# Sheet4.net
KiCad netlist of a schematic drawn in Altium Designer
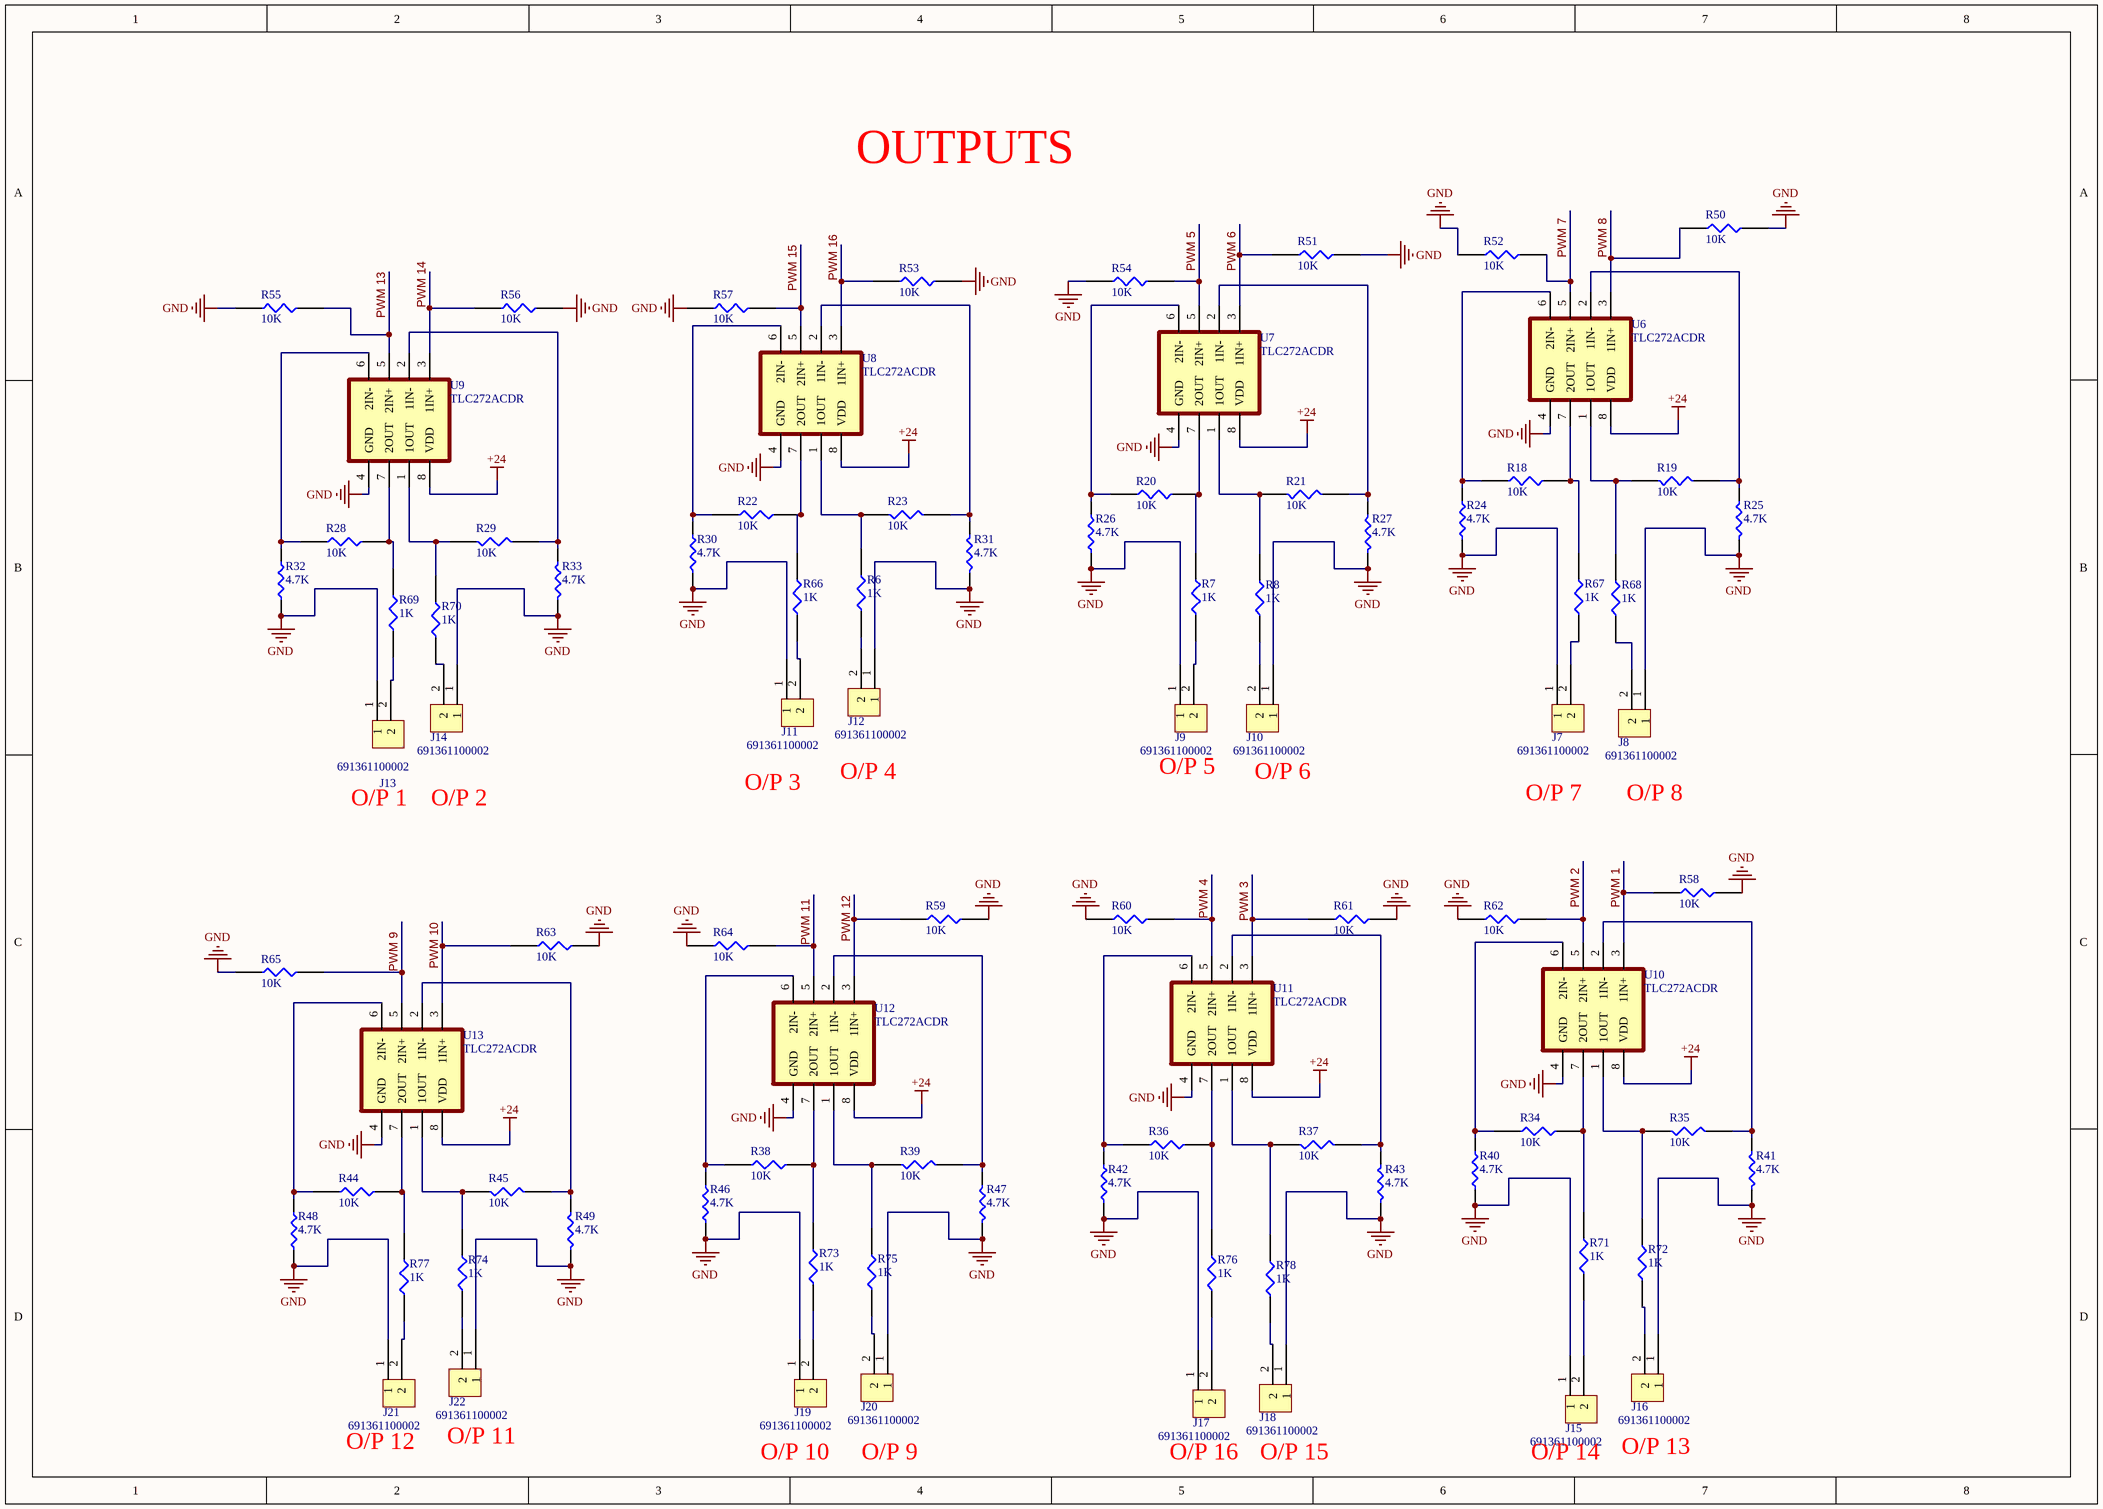
[diagram p0: Sheet4.SchDoc]

(export (version "E")
  (design (tool "Eeschema 10.0.6"))
  (components
    (comp (ref "J7")
      (value "691361100002")
      (footprint "Screw Terminal 3.5mm")
      (description "3611 Series 3.5mm Pitch Straight Pluggable Term Block; Plug; Cable Mount; 2 Way")
      (fields (field (name "MANUFACTURER") "Wurth Electronics") (field (name "VOLTAGE") "300V"))
      (libsource (lib "") (part "Screw Tarminal 3.5mm pitch_1"))
    )
    (comp (ref "J8")
      (value "691361100002")
      (footprint "Screw Terminal 3.5mm")
      (description "3611 Series 3.5mm Pitch Straight Pluggable Term Block; Plug; Cable Mount; 2 Way")
      (fields (field (name "MANUFACTURER") "Wurth Electronics") (field (name "VOLTAGE") "300V"))
      (libsource (lib "Component Schematic Library V1") (part "Screw Tarminal 3.5mm pitch"))
    )
    (comp (ref "J9")
      (value "691361100002")
      (footprint "Screw Terminal 3.5mm")
      (description "3611 Series 3.5mm Pitch Straight Pluggable Term Block; Plug; Cable Mount; 2 Way")
      (fields (field (name "MANUFACTURER") "Wurth Electronics") (field (name "VOLTAGE") "300V"))
      (libsource (lib "") (part "Screw Tarminal 3.5mm pitch_1"))
    )
    (comp (ref "J10")
      (value "691361100002")
      (footprint "Screw Terminal 3.5mm")
      (description "3611 Series 3.5mm Pitch Straight Pluggable Term Block; Plug; Cable Mount; 2 Way")
      (fields (field (name "MANUFACTURER") "Wurth Electronics") (field (name "VOLTAGE") "300V"))
      (libsource (lib "Component Schematic Library V1") (part "Screw Tarminal 3.5mm pitch"))
    )
    (comp (ref "J11")
      (value "691361100002")
      (footprint "Screw Terminal 3.5mm")
      (description "3611 Series 3.5mm Pitch Straight Pluggable Term Block; Plug; Cable Mount; 2 Way")
      (fields (field (name "MANUFACTURER") "Wurth Electronics") (field (name "VOLTAGE") "300V"))
      (libsource (lib "") (part "Screw Tarminal 3.5mm pitch_1"))
    )
    (comp (ref "J12")
      (value "691361100002")
      (footprint "Screw Terminal 3.5mm")
      (description "3611 Series 3.5mm Pitch Straight Pluggable Term Block; Plug; Cable Mount; 2 Way")
      (fields (field (name "MANUFACTURER") "Wurth Electronics") (field (name "VOLTAGE") "300V"))
      (libsource (lib "Component Schematic Library V1") (part "Screw Tarminal 3.5mm pitch"))
    )
    (comp (ref "J13")
      (value "691361100002")
      (footprint "Screw Terminal 3.5mm")
      (description "3611 Series 3.5mm Pitch Straight Pluggable Term Block; Plug; Cable Mount; 2 Way")
      (fields (field (name "MANUFACTURER") "Wurth Electronics") (field (name "VOLTAGE") "300V"))
      (libsource (lib "") (part "Screw Tarminal 3.5mm pitch_1"))
    )
    (comp (ref "J14")
      (value "691361100002")
      (footprint "Screw Terminal 3.5mm")
      (description "3611 Series 3.5mm Pitch Straight Pluggable Term Block; Plug; Cable Mount; 2 Way")
      (fields (field (name "MANUFACTURER") "Wurth Electronics") (field (name "VOLTAGE") "300V"))
      (libsource (lib "Component Schematic Library V1") (part "Screw Tarminal 3.5mm pitch"))
    )
    (comp (ref "J15")
      (value "691361100002")
      (footprint "Screw Terminal 3.5mm")
      (description "3611 Series 3.5mm Pitch Straight Pluggable Term Block; Plug; Cable Mount; 2 Way")
      (fields (field (name "MANUFACTURER") "Wurth Electronics") (field (name "VOLTAGE") "300V"))
      (libsource (lib "") (part "Screw Tarminal 3.5mm pitch_1"))
    )
    (comp (ref "J16")
      (value "691361100002")
      (footprint "Screw Terminal 3.5mm")
      (description "3611 Series 3.5mm Pitch Straight Pluggable Term Block; Plug; Cable Mount; 2 Way")
      (fields (field (name "MANUFACTURER") "Wurth Electronics") (field (name "VOLTAGE") "300V"))
      (libsource (lib "Component Schematic Library V1") (part "Screw Tarminal 3.5mm pitch"))
    )
    (comp (ref "J17")
      (value "691361100002")
      (footprint "Screw Terminal 3.5mm")
      (description "3611 Series 3.5mm Pitch Straight Pluggable Term Block; Plug; Cable Mount; 2 Way")
      (fields (field (name "MANUFACTURER") "Wurth Electronics") (field (name "VOLTAGE") "300V"))
      (libsource (lib "") (part "Screw Tarminal 3.5mm pitch_1"))
    )
    (comp (ref "J18")
      (value "691361100002")
      (footprint "Screw Terminal 3.5mm")
      (description "3611 Series 3.5mm Pitch Straight Pluggable Term Block; Plug; Cable Mount; 2 Way")
      (fields (field (name "MANUFACTURER") "Wurth Electronics") (field (name "VOLTAGE") "300V"))
      (libsource (lib "Component Schematic Library V1") (part "Screw Tarminal 3.5mm pitch"))
    )
    (comp (ref "J19")
      (value "691361100002")
      (footprint "Screw Terminal 3.5mm")
      (description "3611 Series 3.5mm Pitch Straight Pluggable Term Block; Plug; Cable Mount; 2 Way")
      (fields (field (name "MANUFACTURER") "Wurth Electronics") (field (name "VOLTAGE") "300V"))
      (libsource (lib "") (part "Screw Tarminal 3.5mm pitch_1"))
    )
    (comp (ref "J20")
      (value "691361100002")
      (footprint "Screw Terminal 3.5mm")
      (description "3611 Series 3.5mm Pitch Straight Pluggable Term Block; Plug; Cable Mount; 2 Way")
      (fields (field (name "MANUFACTURER") "Wurth Electronics") (field (name "VOLTAGE") "300V"))
      (libsource (lib "Component Schematic Library V1") (part "Screw Tarminal 3.5mm pitch"))
    )
    (comp (ref "J21")
      (value "691361100002")
      (footprint "Screw Terminal 3.5mm")
      (description "3611 Series 3.5mm Pitch Straight Pluggable Term Block; Plug; Cable Mount; 2 Way")
      (fields (field (name "MANUFACTURER") "Wurth Electronics") (field (name "VOLTAGE") "300V"))
      (libsource (lib "") (part "Screw Tarminal 3.5mm pitch_1"))
    )
    (comp (ref "J22")
      (value "691361100002")
      (footprint "Screw Terminal 3.5mm")
      (description "3611 Series 3.5mm Pitch Straight Pluggable Term Block; Plug; Cable Mount; 2 Way")
      (fields (field (name "MANUFACTURER") "Wurth Electronics") (field (name "VOLTAGE") "300V"))
      (libsource (lib "Component Schematic Library V1") (part "Screw Tarminal 3.5mm pitch"))
    )
    (comp (ref "R6")
      (value "1K")
      (footprint "R_0805")
      (description "贴片电阻 1000Ω ± 1.00% 0.125W ± 100ppm/℃ 0805")
      (fields
        (field (name "MANUFACTURER") "Yageo")
        (field (name "MANUFACTURER PART NUMBER") "RC0805FR-071KL")
      )
      (libsource (lib "Component Schematic Library V1") (part "RES_1_K_0805"))
    )
    (comp (ref "R7")
      (value "1K")
      (footprint "R_0805")
      (description "贴片电阻 1000Ω ± 1.00% 0.125W ± 100ppm/℃ 0805")
      (fields
        (field (name "MANUFACTURER") "Yageo")
        (field (name "MANUFACTURER PART NUMBER") "RC0805FR-071KL")
      )
      (libsource (lib "Component Schematic Library V1") (part "RES_1_K_0805"))
    )
    (comp (ref "R8")
      (value "1K")
      (footprint "R_0805")
      (description "贴片电阻 1000Ω ± 1.00% 0.125W ± 100ppm/℃ 0805")
      (fields
        (field (name "MANUFACTURER") "Yageo")
        (field (name "MANUFACTURER PART NUMBER") "RC0805FR-071KL")
      )
      (libsource (lib "Component Schematic Library V1") (part "RES_1_K_0805"))
    )
    (comp (ref "R18")
      (value "10K")
      (footprint "R_0805")
      (description "贴片电阻 10000Ω ± 1.00% 0.125W ± 100ppm/℃ 0805")
      (fields
        (field (name "MANUFACTURER") "Yageo")
        (field (name "MANUFACTURER PART NUMBER") "RC0805FR-0710KL")
      )
      (libsource (lib "Component Schematic Library V1") (part "RES_10_K_0805"))
    )
    (comp (ref "R19")
      (value "10K")
      (footprint "R_0805")
      (description "贴片电阻 10000Ω ± 1.00% 0.125W ± 100ppm/℃ 0805")
      (fields
        (field (name "MANUFACTURER") "Yageo")
        (field (name "MANUFACTURER PART NUMBER") "RC0805FR-0710KL")
      )
      (libsource (lib "Component Schematic Library V1") (part "RES_10_K_0805"))
    )
    (comp (ref "R20")
      (value "10K")
      (footprint "R_0805")
      (description "贴片电阻 10000Ω ± 1.00% 0.125W ± 100ppm/℃ 0805")
      (fields
        (field (name "MANUFACTURER") "Yageo")
        (field (name "MANUFACTURER PART NUMBER") "RC0805FR-0710KL")
      )
      (libsource (lib "Component Schematic Library V1") (part "RES_10_K_0805"))
    )
    (comp (ref "R21")
      (value "10K")
      (footprint "R_0805")
      (description "贴片电阻 10000Ω ± 1.00% 0.125W ± 100ppm/℃ 0805")
      (fields
        (field (name "MANUFACTURER") "Yageo")
        (field (name "MANUFACTURER PART NUMBER") "RC0805FR-0710KL")
      )
      (libsource (lib "Component Schematic Library V1") (part "RES_10_K_0805"))
    )
    (comp (ref "R22")
      (value "10K")
      (footprint "R_0805")
      (description "贴片电阻 10000Ω ± 1.00% 0.125W ± 100ppm/℃ 0805")
      (fields
        (field (name "MANUFACTURER") "Yageo")
        (field (name "MANUFACTURER PART NUMBER") "RC0805FR-0710KL")
      )
      (libsource (lib "Component Schematic Library V1") (part "RES_10_K_0805"))
    )
    (comp (ref "R23")
      (value "10K")
      (footprint "R_0805")
      (description "贴片电阻 10000Ω ± 1.00% 0.125W ± 100ppm/℃ 0805")
      (fields
        (field (name "MANUFACTURER") "Yageo")
        (field (name "MANUFACTURER PART NUMBER") "RC0805FR-0710KL")
      )
      (libsource (lib "Component Schematic Library V1") (part "RES_10_K_0805"))
    )
    (comp (ref "R24")
      (value "4.7K")
      (footprint "R_0805")
      (description "Res Thick Film 0805 4.7K Ohm 1% 0.125W ±100ppm/°C Molded SMD Paper T/R")
      (fields
        (field (name "MANUFACTURER") "Stackpole Electronics")
        (field (name "MANUFACTURER PART NUMBER") "RMCF0805FT4K70")
      )
      (libsource (lib "Component Schematic Library V1") (part "Res 4.7 K"))
    )
    (comp (ref "R25")
      (value "4.7K")
      (footprint "R_0805")
      (description "Res Thick Film 0805 4.7K Ohm 1% 0.125W ±100ppm/°C Molded SMD Paper T/R")
      (fields
        (field (name "MANUFACTURER") "Stackpole Electronics")
        (field (name "MANUFACTURER PART NUMBER") "RMCF0805FT4K70")
      )
      (libsource (lib "Component Schematic Library V1") (part "Res 4.7 K"))
    )
    (comp (ref "R26")
      (value "4.7K")
      (footprint "R_0805")
      (description "Res Thick Film 0805 4.7K Ohm 1% 0.125W ±100ppm/°C Molded SMD Paper T/R")
      (fields
        (field (name "MANUFACTURER") "Stackpole Electronics")
        (field (name "MANUFACTURER PART NUMBER") "RMCF0805FT4K70")
      )
      (libsource (lib "Component Schematic Library V1") (part "Res 4.7 K"))
    )
    (comp (ref "R27")
      (value "4.7K")
      (footprint "R_0805")
      (description "Res Thick Film 0805 4.7K Ohm 1% 0.125W ±100ppm/°C Molded SMD Paper T/R")
      (fields
        (field (name "MANUFACTURER") "Stackpole Electronics")
        (field (name "MANUFACTURER PART NUMBER") "RMCF0805FT4K70")
      )
      (libsource (lib "Component Schematic Library V1") (part "Res 4.7 K"))
    )
    (comp (ref "R28")
      (value "10K")
      (footprint "R_0805")
      (description "贴片电阻 10000Ω ± 1.00% 0.125W ± 100ppm/℃ 0805")
      (fields
        (field (name "MANUFACTURER") "Yageo")
        (field (name "MANUFACTURER PART NUMBER") "RC0805FR-0710KL")
      )
      (libsource (lib "Component Schematic Library V1") (part "RES_10_K_0805"))
    )
    (comp (ref "R29")
      (value "10K")
      (footprint "R_0805")
      (description "贴片电阻 10000Ω ± 1.00% 0.125W ± 100ppm/℃ 0805")
      (fields
        (field (name "MANUFACTURER") "Yageo")
        (field (name "MANUFACTURER PART NUMBER") "RC0805FR-0710KL")
      )
      (libsource (lib "Component Schematic Library V1") (part "RES_10_K_0805"))
    )
    (comp (ref "R30")
      (value "4.7K")
      (footprint "R_0805")
      (description "Res Thick Film 0805 4.7K Ohm 1% 0.125W ±100ppm/°C Molded SMD Paper T/R")
      (fields
        (field (name "MANUFACTURER") "Stackpole Electronics")
        (field (name "MANUFACTURER PART NUMBER") "RMCF0805FT4K70")
      )
      (libsource (lib "Component Schematic Library V1") (part "Res 4.7 K"))
    )
    (comp (ref "R31")
      (value "4.7K")
      (footprint "R_0805")
      (description "Res Thick Film 0805 4.7K Ohm 1% 0.125W ±100ppm/°C Molded SMD Paper T/R")
      (fields
        (field (name "MANUFACTURER") "Stackpole Electronics")
        (field (name "MANUFACTURER PART NUMBER") "RMCF0805FT4K70")
      )
      (libsource (lib "Component Schematic Library V1") (part "Res 4.7 K"))
    )
    (comp (ref "R32")
      (value "4.7K")
      (footprint "R_0805")
      (description "Res Thick Film 0805 4.7K Ohm 1% 0.125W ±100ppm/°C Molded SMD Paper T/R")
      (fields
        (field (name "MANUFACTURER") "Stackpole Electronics")
        (field (name "MANUFACTURER PART NUMBER") "RMCF0805FT4K70")
      )
      (libsource (lib "Component Schematic Library V1") (part "Res 4.7 K"))
    )
    (comp (ref "R33")
      (value "4.7K")
      (footprint "R_0805")
      (description "Res Thick Film 0805 4.7K Ohm 1% 0.125W ±100ppm/°C Molded SMD Paper T/R")
      (fields
        (field (name "MANUFACTURER") "Stackpole Electronics")
        (field (name "MANUFACTURER PART NUMBER") "RMCF0805FT4K70")
      )
      (libsource (lib "Component Schematic Library V1") (part "Res 4.7 K"))
    )
    (comp (ref "R34")
      (value "10K")
      (footprint "R_0805")
      (description "贴片电阻 10000Ω ± 1.00% 0.125W ± 100ppm/℃ 0805")
      (fields
        (field (name "MANUFACTURER") "Yageo")
        (field (name "MANUFACTURER PART NUMBER") "RC0805FR-0710KL")
      )
      (libsource (lib "Component Schematic Library V1") (part "RES_10_K_0805"))
    )
    (comp (ref "R35")
      (value "10K")
      (footprint "R_0805")
      (description "贴片电阻 10000Ω ± 1.00% 0.125W ± 100ppm/℃ 0805")
      (fields
        (field (name "MANUFACTURER") "Yageo")
        (field (name "MANUFACTURER PART NUMBER") "RC0805FR-0710KL")
      )
      (libsource (lib "Component Schematic Library V1") (part "RES_10_K_0805"))
    )
    (comp (ref "R36")
      (value "10K")
      (footprint "R_0805")
      (description "贴片电阻 10000Ω ± 1.00% 0.125W ± 100ppm/℃ 0805")
      (fields
        (field (name "MANUFACTURER") "Yageo")
        (field (name "MANUFACTURER PART NUMBER") "RC0805FR-0710KL")
      )
      (libsource (lib "Component Schematic Library V1") (part "RES_10_K_0805"))
    )
    (comp (ref "R37")
      (value "10K")
      (footprint "R_0805")
      (description "贴片电阻 10000Ω ± 1.00% 0.125W ± 100ppm/℃ 0805")
      (fields
        (field (name "MANUFACTURER") "Yageo")
        (field (name "MANUFACTURER PART NUMBER") "RC0805FR-0710KL")
      )
      (libsource (lib "Component Schematic Library V1") (part "RES_10_K_0805"))
    )
    (comp (ref "R38")
      (value "10K")
      (footprint "R_0805")
      (description "贴片电阻 10000Ω ± 1.00% 0.125W ± 100ppm/℃ 0805")
      (fields
        (field (name "MANUFACTURER") "Yageo")
        (field (name "MANUFACTURER PART NUMBER") "RC0805FR-0710KL")
      )
      (libsource (lib "Component Schematic Library V1") (part "RES_10_K_0805"))
    )
    (comp (ref "R39")
      (value "10K")
      (footprint "R_0805")
      (description "贴片电阻 10000Ω ± 1.00% 0.125W ± 100ppm/℃ 0805")
      (fields
        (field (name "MANUFACTURER") "Yageo")
        (field (name "MANUFACTURER PART NUMBER") "RC0805FR-0710KL")
      )
      (libsource (lib "Component Schematic Library V1") (part "RES_10_K_0805"))
    )
    (comp (ref "R40")
      (value "4.7K")
      (footprint "R_0805")
      (description "Res Thick Film 0805 4.7K Ohm 1% 0.125W ±100ppm/°C Molded SMD Paper T/R")
      (fields
        (field (name "MANUFACTURER") "Stackpole Electronics")
        (field (name "MANUFACTURER PART NUMBER") "RMCF0805FT4K70")
      )
      (libsource (lib "Component Schematic Library V1") (part "Res 4.7 K"))
    )
    (comp (ref "R41")
      (value "4.7K")
      (footprint "R_0805")
      (description "Res Thick Film 0805 4.7K Ohm 1% 0.125W ±100ppm/°C Molded SMD Paper T/R")
      (fields
        (field (name "MANUFACTURER") "Stackpole Electronics")
        (field (name "MANUFACTURER PART NUMBER") "RMCF0805FT4K70")
      )
      (libsource (lib "Component Schematic Library V1") (part "Res 4.7 K"))
    )
    (comp (ref "R42")
      (value "4.7K")
      (footprint "R_0805")
      (description "Res Thick Film 0805 4.7K Ohm 1% 0.125W ±100ppm/°C Molded SMD Paper T/R")
      (fields
        (field (name "MANUFACTURER") "Stackpole Electronics")
        (field (name "MANUFACTURER PART NUMBER") "RMCF0805FT4K70")
      )
      (libsource (lib "Component Schematic Library V1") (part "Res 4.7 K"))
    )
    (comp (ref "R43")
      (value "4.7K")
      (footprint "R_0805")
      (description "Res Thick Film 0805 4.7K Ohm 1% 0.125W ±100ppm/°C Molded SMD Paper T/R")
      (fields
        (field (name "MANUFACTURER") "Stackpole Electronics")
        (field (name "MANUFACTURER PART NUMBER") "RMCF0805FT4K70")
      )
      (libsource (lib "Component Schematic Library V1") (part "Res 4.7 K"))
    )
    (comp (ref "R44")
      (value "10K")
      (footprint "R_0805")
      (description "贴片电阻 10000Ω ± 1.00% 0.125W ± 100ppm/℃ 0805")
      (fields
        (field (name "MANUFACTURER") "Yageo")
        (field (name "MANUFACTURER PART NUMBER") "RC0805FR-0710KL")
      )
      (libsource (lib "Component Schematic Library V1") (part "RES_10_K_0805"))
    )
    (comp (ref "R45")
      (value "10K")
      (footprint "R_0805")
      (description "贴片电阻 10000Ω ± 1.00% 0.125W ± 100ppm/℃ 0805")
      (fields
        (field (name "MANUFACTURER") "Yageo")
        (field (name "MANUFACTURER PART NUMBER") "RC0805FR-0710KL")
      )
      (libsource (lib "Component Schematic Library V1") (part "RES_10_K_0805"))
    )
    (comp (ref "R46")
      (value "4.7K")
      (footprint "R_0805")
      (description "Res Thick Film 0805 4.7K Ohm 1% 0.125W ±100ppm/°C Molded SMD Paper T/R")
      (fields
        (field (name "MANUFACTURER") "Stackpole Electronics")
        (field (name "MANUFACTURER PART NUMBER") "RMCF0805FT4K70")
      )
      (libsource (lib "Component Schematic Library V1") (part "Res 4.7 K"))
    )
    (comp (ref "R47")
      (value "4.7K")
      (footprint "R_0805")
      (description "Res Thick Film 0805 4.7K Ohm 1% 0.125W ±100ppm/°C Molded SMD Paper T/R")
      (fields
        (field (name "MANUFACTURER") "Stackpole Electronics")
        (field (name "MANUFACTURER PART NUMBER") "RMCF0805FT4K70")
      )
      (libsource (lib "Component Schematic Library V1") (part "Res 4.7 K"))
    )
    (comp (ref "R48")
      (value "4.7K")
      (footprint "R_0805")
      (description "Res Thick Film 0805 4.7K Ohm 1% 0.125W ±100ppm/°C Molded SMD Paper T/R")
      (fields
        (field (name "MANUFACTURER") "Stackpole Electronics")
        (field (name "MANUFACTURER PART NUMBER") "RMCF0805FT4K70")
      )
      (libsource (lib "Component Schematic Library V1") (part "Res 4.7 K"))
    )
    (comp (ref "R49")
      (value "4.7K")
      (footprint "R_0805")
      (description "Res Thick Film 0805 4.7K Ohm 1% 0.125W ±100ppm/°C Molded SMD Paper T/R")
      (fields
        (field (name "MANUFACTURER") "Stackpole Electronics")
        (field (name "MANUFACTURER PART NUMBER") "RMCF0805FT4K70")
      )
      (libsource (lib "Component Schematic Library V1") (part "Res 4.7 K"))
    )
    (comp (ref "R50")
      (value "10K")
      (footprint "R_0805")
      (description "贴片电阻 10000Ω ± 1.00% 0.125W ± 100ppm/℃ 0805")
      (fields
        (field (name "MANUFACTURER") "Yageo")
        (field (name "MANUFACTURER PART NUMBER") "RC0805FR-0710KL")
      )
      (libsource (lib "Component Schematic Library V1") (part "RES_10_K_0805"))
    )
    (comp (ref "R51")
      (value "10K")
      (footprint "R_0805")
      (description "贴片电阻 10000Ω ± 1.00% 0.125W ± 100ppm/℃ 0805")
      (fields
        (field (name "MANUFACTURER") "Yageo")
        (field (name "MANUFACTURER PART NUMBER") "RC0805FR-0710KL")
      )
      (libsource (lib "Component Schematic Library V1") (part "RES_10_K_0805"))
    )
    (comp (ref "R52")
      (value "10K")
      (footprint "R_0805")
      (description "贴片电阻 10000Ω ± 1.00% 0.125W ± 100ppm/℃ 0805")
      (fields
        (field (name "MANUFACTURER") "Yageo")
        (field (name "MANUFACTURER PART NUMBER") "RC0805FR-0710KL")
      )
      (libsource (lib "Component Schematic Library V1") (part "RES_10_K_0805"))
    )
    (comp (ref "R53")
      (value "10K")
      (footprint "R_0805")
      (description "贴片电阻 10000Ω ± 1.00% 0.125W ± 100ppm/℃ 0805")
      (fields
        (field (name "MANUFACTURER") "Yageo")
        (field (name "MANUFACTURER PART NUMBER") "RC0805FR-0710KL")
      )
      (libsource (lib "Component Schematic Library V1") (part "RES_10_K_0805"))
    )
    (comp (ref "R54")
      (value "10K")
      (footprint "R_0805")
      (description "贴片电阻 10000Ω ± 1.00% 0.125W ± 100ppm/℃ 0805")
      (fields
        (field (name "MANUFACTURER") "Yageo")
        (field (name "MANUFACTURER PART NUMBER") "RC0805FR-0710KL")
      )
      (libsource (lib "Component Schematic Library V1") (part "RES_10_K_0805"))
    )
    (comp (ref "R55")
      (value "10K")
      (footprint "R_0805")
      (description "贴片电阻 10000Ω ± 1.00% 0.125W ± 100ppm/℃ 0805")
      (fields
        (field (name "MANUFACTURER") "Yageo")
        (field (name "MANUFACTURER PART NUMBER") "RC0805FR-0710KL")
      )
      (libsource (lib "Component Schematic Library V1") (part "RES_10_K_0805"))
    )
    (comp (ref "R56")
      (value "10K")
      (footprint "R_0805")
      (description "贴片电阻 10000Ω ± 1.00% 0.125W ± 100ppm/℃ 0805")
      (fields
        (field (name "MANUFACTURER") "Yageo")
        (field (name "MANUFACTURER PART NUMBER") "RC0805FR-0710KL")
      )
      (libsource (lib "Component Schematic Library V1") (part "RES_10_K_0805"))
    )
    (comp (ref "R57")
      (value "10K")
      (footprint "R_0805")
      (description "贴片电阻 10000Ω ± 1.00% 0.125W ± 100ppm/℃ 0805")
      (fields
        (field (name "MANUFACTURER") "Yageo")
        (field (name "MANUFACTURER PART NUMBER") "RC0805FR-0710KL")
      )
      (libsource (lib "Component Schematic Library V1") (part "RES_10_K_0805"))
    )
    (comp (ref "R58")
      (value "10K")
      (footprint "R_0805")
      (description "贴片电阻 10000Ω ± 1.00% 0.125W ± 100ppm/℃ 0805")
      (fields
        (field (name "MANUFACTURER") "Yageo")
        (field (name "MANUFACTURER PART NUMBER") "RC0805FR-0710KL")
      )
      (libsource (lib "Component Schematic Library V1") (part "RES_10_K_0805"))
    )
    (comp (ref "R59")
      (value "10K")
      (footprint "R_0805")
      (description "贴片电阻 10000Ω ± 1.00% 0.125W ± 100ppm/℃ 0805")
      (fields
        (field (name "MANUFACTURER") "Yageo")
        (field (name "MANUFACTURER PART NUMBER") "RC0805FR-0710KL")
      )
      (libsource (lib "Component Schematic Library V1") (part "RES_10_K_0805"))
    )
    (comp (ref "R60")
      (value "10K")
      (footprint "R_0805")
      (description "贴片电阻 10000Ω ± 1.00% 0.125W ± 100ppm/℃ 0805")
      (fields
        (field (name "MANUFACTURER") "Yageo")
        (field (name "MANUFACTURER PART NUMBER") "RC0805FR-0710KL")
      )
      (libsource (lib "Component Schematic Library V1") (part "RES_10_K_0805"))
    )
    (comp (ref "R61")
      (value "10K")
      (footprint "R_0805")
      (description "贴片电阻 10000Ω ± 1.00% 0.125W ± 100ppm/℃ 0805")
      (fields
        (field (name "MANUFACTURER") "Yageo")
        (field (name "MANUFACTURER PART NUMBER") "RC0805FR-0710KL")
      )
      (libsource (lib "Component Schematic Library V1") (part "RES_10_K_0805"))
    )
    (comp (ref "R62")
      (value "10K")
      (footprint "R_0805")
      (description "贴片电阻 10000Ω ± 1.00% 0.125W ± 100ppm/℃ 0805")
      (fields
        (field (name "MANUFACTURER") "Yageo")
        (field (name "MANUFACTURER PART NUMBER") "RC0805FR-0710KL")
      )
      (libsource (lib "Component Schematic Library V1") (part "RES_10_K_0805"))
    )
    (comp (ref "R63")
      (value "10K")
      (footprint "R_0805")
      (description "贴片电阻 10000Ω ± 1.00% 0.125W ± 100ppm/℃ 0805")
      (fields
        (field (name "MANUFACTURER") "Yageo")
        (field (name "MANUFACTURER PART NUMBER") "RC0805FR-0710KL")
      )
      (libsource (lib "Component Schematic Library V1") (part "RES_10_K_0805"))
    )
    (comp (ref "R64")
      (value "10K")
      (footprint "R_0805")
      (description "贴片电阻 10000Ω ± 1.00% 0.125W ± 100ppm/℃ 0805")
      (fields
        (field (name "MANUFACTURER") "Yageo")
        (field (name "MANUFACTURER PART NUMBER") "RC0805FR-0710KL")
      )
      (libsource (lib "Component Schematic Library V1") (part "RES_10_K_0805"))
    )
    (comp (ref "R65")
      (value "10K")
      (footprint "R_0805")
      (description "贴片电阻 10000Ω ± 1.00% 0.125W ± 100ppm/℃ 0805")
      (fields
        (field (name "MANUFACTURER") "Yageo")
        (field (name "MANUFACTURER PART NUMBER") "RC0805FR-0710KL")
      )
      (libsource (lib "Component Schematic Library V1") (part "RES_10_K_0805"))
    )
    (comp (ref "R66")
      (value "1K")
      (footprint "R_0805")
      (description "贴片电阻 1000Ω ± 1.00% 0.125W ± 100ppm/℃ 0805")
      (fields
        (field (name "MANUFACTURER") "Yageo")
        (field (name "MANUFACTURER PART NUMBER") "RC0805FR-071KL")
      )
      (libsource (lib "Component Schematic Library V1") (part "RES_1_K_0805"))
    )
    (comp (ref "R67")
      (value "1K")
      (footprint "R_0805")
      (description "贴片电阻 1000Ω ± 1.00% 0.125W ± 100ppm/℃ 0805")
      (fields
        (field (name "MANUFACTURER") "Yageo")
        (field (name "MANUFACTURER PART NUMBER") "RC0805FR-071KL")
      )
      (libsource (lib "Component Schematic Library V1") (part "RES_1_K_0805"))
    )
    (comp (ref "R68")
      (value "1K")
      (footprint "R_0805")
      (description "贴片电阻 1000Ω ± 1.00% 0.125W ± 100ppm/℃ 0805")
      (fields
        (field (name "MANUFACTURER") "Yageo")
        (field (name "MANUFACTURER PART NUMBER") "RC0805FR-071KL")
      )
      (libsource (lib "Component Schematic Library V1") (part "RES_1_K_0805"))
    )
    (comp (ref "R69")
      (value "1K")
      (footprint "R_0805")
      (description "贴片电阻 1000Ω ± 1.00% 0.125W ± 100ppm/℃ 0805")
      (fields
        (field (name "MANUFACTURER") "Yageo")
        (field (name "MANUFACTURER PART NUMBER") "RC0805FR-071KL")
      )
      (libsource (lib "Component Schematic Library V1") (part "RES_1_K_0805"))
    )
    (comp (ref "R70")
      (value "1K")
      (footprint "R_0805")
      (description "贴片电阻 1000Ω ± 1.00% 0.125W ± 100ppm/℃ 0805")
      (fields
        (field (name "MANUFACTURER") "Yageo")
        (field (name "MANUFACTURER PART NUMBER") "RC0805FR-071KL")
      )
      (libsource (lib "Component Schematic Library V1") (part "RES_1_K_0805"))
    )
    (comp (ref "R71")
      (value "1K")
      (footprint "R_0805")
      (description "贴片电阻 1000Ω ± 1.00% 0.125W ± 100ppm/℃ 0805")
      (fields
        (field (name "MANUFACTURER") "Yageo")
        (field (name "MANUFACTURER PART NUMBER") "RC0805FR-071KL")
      )
      (libsource (lib "Component Schematic Library V1") (part "RES_1_K_0805"))
    )
    (comp (ref "R72")
      (value "1K")
      (footprint "R_0805")
      (description "贴片电阻 1000Ω ± 1.00% 0.125W ± 100ppm/℃ 0805")
      (fields
        (field (name "MANUFACTURER") "Yageo")
        (field (name "MANUFACTURER PART NUMBER") "RC0805FR-071KL")
      )
      (libsource (lib "Component Schematic Library V1") (part "RES_1_K_0805"))
    )
    (comp (ref "R73")
      (value "1K")
      (footprint "R_0805")
      (description "贴片电阻 1000Ω ± 1.00% 0.125W ± 100ppm/℃ 0805")
      (fields
        (field (name "MANUFACTURER") "Yageo")
        (field (name "MANUFACTURER PART NUMBER") "RC0805FR-071KL")
      )
      (libsource (lib "Component Schematic Library V1") (part "RES_1_K_0805"))
    )
    (comp (ref "R74")
      (value "1K")
      (footprint "R_0805")
      (description "贴片电阻 1000Ω ± 1.00% 0.125W ± 100ppm/℃ 0805")
      (fields
        (field (name "MANUFACTURER") "Yageo")
        (field (name "MANUFACTURER PART NUMBER") "RC0805FR-071KL")
      )
      (libsource (lib "Component Schematic Library V1") (part "RES_1_K_0805"))
    )
    (comp (ref "R75")
      (value "1K")
      (footprint "R_0805")
      (description "贴片电阻 1000Ω ± 1.00% 0.125W ± 100ppm/℃ 0805")
      (fields
        (field (name "MANUFACTURER") "Yageo")
        (field (name "MANUFACTURER PART NUMBER") "RC0805FR-071KL")
      )
      (libsource (lib "Component Schematic Library V1") (part "RES_1_K_0805"))
    )
    (comp (ref "R76")
      (value "1K")
      (footprint "R_0805")
      (description "贴片电阻 1000Ω ± 1.00% 0.125W ± 100ppm/℃ 0805")
      (fields
        (field (name "MANUFACTURER") "Yageo")
        (field (name "MANUFACTURER PART NUMBER") "RC0805FR-071KL")
      )
      (libsource (lib "Component Schematic Library V1") (part "RES_1_K_0805"))
    )
    (comp (ref "R77")
      (value "1K")
      (footprint "R_0805")
      (description "贴片电阻 1000Ω ± 1.00% 0.125W ± 100ppm/℃ 0805")
      (fields
        (field (name "MANUFACTURER") "Yageo")
        (field (name "MANUFACTURER PART NUMBER") "RC0805FR-071KL")
      )
      (libsource (lib "Component Schematic Library V1") (part "RES_1_K_0805"))
    )
    (comp (ref "R78")
      (value "1K")
      (footprint "R_0805")
      (description "贴片电阻 1000Ω ± 1.00% 0.125W ± 100ppm/℃ 0805")
      (fields
        (field (name "MANUFACTURER") "Yageo")
        (field (name "MANUFACTURER PART NUMBER") "RC0805FR-071KL")
      )
      (libsource (lib "Component Schematic Library V1") (part "RES_1_K_0805"))
    )
    (comp (ref "U6")
      (value "TLC272ACDR")
      (footprint "8 SOIC")
      (description "Op Amp, 1.7MHZ, 3.6V/US, SOIC-8; Bandwid; Msl: Msl 1 - Unlimited; Svhc: No Svhc (15-JAN-2019)")
      (fields (field (name "MANUFACTURER") "Texas Instruments"))
      (libsource (lib "Component Schematic Library V1") (part "TLC272ACDR"))
    )
    (comp (ref "U7")
      (value "TLC272ACDR")
      (footprint "8 SOIC")
      (description "Op Amp, 1.7MHZ, 3.6V/US, SOIC-8; Bandwid; Msl: Msl 1 - Unlimited; Svhc: No Svhc (15-JAN-2019)")
      (fields (field (name "MANUFACTURER") "Texas Instruments"))
      (libsource (lib "Component Schematic Library V1") (part "TLC272ACDR"))
    )
    (comp (ref "U8")
      (value "TLC272ACDR")
      (footprint "8 SOIC")
      (description "Op Amp, 1.7MHZ, 3.6V/US, SOIC-8; Bandwid; Msl: Msl 1 - Unlimited; Svhc: No Svhc (15-JAN-2019)")
      (fields (field (name "MANUFACTURER") "Texas Instruments"))
      (libsource (lib "Component Schematic Library V1") (part "TLC272ACDR"))
    )
    (comp (ref "U9")
      (value "TLC272ACDR")
      (footprint "8 SOIC")
      (description "Op Amp, 1.7MHZ, 3.6V/US, SOIC-8; Bandwid; Msl: Msl 1 - Unlimited; Svhc: No Svhc (15-JAN-2019)")
      (fields (field (name "MANUFACTURER") "Texas Instruments"))
      (libsource (lib "Component Schematic Library V1") (part "TLC272ACDR"))
    )
    (comp (ref "U10")
      (value "TLC272ACDR")
      (footprint "8 SOIC")
      (description "Op Amp, 1.7MHZ, 3.6V/US, SOIC-8; Bandwid; Msl: Msl 1 - Unlimited; Svhc: No Svhc (15-JAN-2019)")
      (fields (field (name "MANUFACTURER") "Texas Instruments"))
      (libsource (lib "Component Schematic Library V1") (part "TLC272ACDR"))
    )
    (comp (ref "U11")
      (value "TLC272ACDR")
      (footprint "8 SOIC")
      (description "Op Amp, 1.7MHZ, 3.6V/US, SOIC-8; Bandwid; Msl: Msl 1 - Unlimited; Svhc: No Svhc (15-JAN-2019)")
      (fields (field (name "MANUFACTURER") "Texas Instruments"))
      (libsource (lib "Component Schematic Library V1") (part "TLC272ACDR"))
    )
    (comp (ref "U12")
      (value "TLC272ACDR")
      (footprint "8 SOIC")
      (description "Op Amp, 1.7MHZ, 3.6V/US, SOIC-8; Bandwid; Msl: Msl 1 - Unlimited; Svhc: No Svhc (15-JAN-2019)")
      (fields (field (name "MANUFACTURER") "Texas Instruments"))
      (libsource (lib "Component Schematic Library V1") (part "TLC272ACDR"))
    )
    (comp (ref "U13")
      (value "TLC272ACDR")
      (footprint "8 SOIC")
      (description "Op Amp, 1.7MHZ, 3.6V/US, SOIC-8; Bandwid; Msl: Msl 1 - Unlimited; Svhc: No Svhc (15-JAN-2019)")
      (fields (field (name "MANUFACTURER") "Texas Instruments"))
      (libsource (lib "Component Schematic Library V1") (part "TLC272ACDR"))
    )
  )
  (nets
    (net (code "1") (name "+24") (class "Default")
      (node (ref "U10") (pin "8") (pinfunction "VDD_8") (pintype "passive"))
      (node (ref "U11") (pin "8") (pinfunction "VDD_8") (pintype "passive"))
      (node (ref "U12") (pin "8") (pinfunction "VDD_8") (pintype "passive"))
      (node (ref "U13") (pin "8") (pinfunction "VDD_8") (pintype "passive"))
      (node (ref "U6") (pin "8") (pinfunction "VDD_8") (pintype "passive"))
      (node (ref "U7") (pin "8") (pinfunction "VDD_8") (pintype "passive"))
      (node (ref "U8") (pin "8") (pinfunction "VDD_8") (pintype "passive"))
      (node (ref "U9") (pin "8") (pinfunction "VDD_8") (pintype "passive"))
    )
    (net (code "2") (name "/PWM 1") (class "Default")
      (node (ref "R58") (pin "1") (pinfunction "2_1") (pintype "passive"))
      (node (ref "U10") (pin "3") (pinfunction "1IN+_3") (pintype "passive"))
    )
    (net (code "3") (name "/PWM 2") (class "Default")
      (node (ref "R62") (pin "2") (pinfunction "3_2") (pintype "passive"))
      (node (ref "U10") (pin "5") (pinfunction "2IN+_5") (pintype "passive"))
    )
    (net (code "4") (name "/PWM 3") (class "Default")
      (node (ref "R61") (pin "1") (pinfunction "2_1") (pintype "passive"))
      (node (ref "U11") (pin "3") (pinfunction "1IN+_3") (pintype "passive"))
    )
    (net (code "5") (name "/PWM 4") (class "Default")
      (node (ref "R60") (pin "2") (pinfunction "3_2") (pintype "passive"))
      (node (ref "U11") (pin "5") (pinfunction "2IN+_5") (pintype "passive"))
    )
    (net (code "6") (name "/PWM 5") (class "Default")
      (node (ref "R54") (pin "2") (pinfunction "3_2") (pintype "passive"))
      (node (ref "U7") (pin "5") (pinfunction "2IN+_5") (pintype "passive"))
    )
    (net (code "7") (name "/PWM 6") (class "Default")
      (node (ref "R51") (pin "1") (pinfunction "2_1") (pintype "passive"))
      (node (ref "U7") (pin "3") (pinfunction "1IN+_3") (pintype "passive"))
    )
    (net (code "8") (name "/PWM 7") (class "Default")
      (node (ref "R52") (pin "2") (pinfunction "3_2") (pintype "passive"))
      (node (ref "U6") (pin "5") (pinfunction "2IN+_5") (pintype "passive"))
    )
    (net (code "9") (name "/PWM 8") (class "Default")
      (node (ref "R50") (pin "1") (pinfunction "2_1") (pintype "passive"))
      (node (ref "U6") (pin "3") (pinfunction "1IN+_3") (pintype "passive"))
    )
    (net (code "10") (name "/PWM 9") (class "Default")
      (node (ref "R65") (pin "2") (pinfunction "3_2") (pintype "passive"))
      (node (ref "U13") (pin "5") (pinfunction "2IN+_5") (pintype "passive"))
    )
    (net (code "11") (name "/PWM 10") (class "Default")
      (node (ref "R63") (pin "1") (pinfunction "2_1") (pintype "passive"))
      (node (ref "U13") (pin "3") (pinfunction "1IN+_3") (pintype "passive"))
    )
    (net (code "12") (name "/PWM 11") (class "Default")
      (node (ref "R64") (pin "2") (pinfunction "3_2") (pintype "passive"))
      (node (ref "U12") (pin "5") (pinfunction "2IN+_5") (pintype "passive"))
    )
    (net (code "13") (name "/PWM 12") (class "Default")
      (node (ref "R59") (pin "1") (pinfunction "2_1") (pintype "passive"))
      (node (ref "U12") (pin "3") (pinfunction "1IN+_3") (pintype "passive"))
    )
    (net (code "14") (name "/PWM 13") (class "Default")
      (node (ref "R55") (pin "2") (pinfunction "3_2") (pintype "passive"))
      (node (ref "U9") (pin "5") (pinfunction "2IN+_5") (pintype "passive"))
    )
    (net (code "15") (name "/PWM 14") (class "Default")
      (node (ref "R56") (pin "1") (pinfunction "2_1") (pintype "passive"))
      (node (ref "U9") (pin "3") (pinfunction "1IN+_3") (pintype "passive"))
    )
    (net (code "16") (name "/PWM 15") (class "Default")
      (node (ref "R57") (pin "2") (pinfunction "3_2") (pintype "passive"))
      (node (ref "U8") (pin "5") (pinfunction "2IN+_5") (pintype "passive"))
    )
    (net (code "17") (name "/PWM 16") (class "Default")
      (node (ref "R53") (pin "1") (pinfunction "2_1") (pintype "passive"))
      (node (ref "U8") (pin "3") (pinfunction "1IN+_3") (pintype "passive"))
    )
    (net (code "18") (name "GND") (class "Default")
      (node (ref "J10") (pin "1") (pinfunction "1_1") (pintype "passive"))
      (node (ref "J11") (pin "1") (pinfunction "1_1") (pintype "passive"))
      (node (ref "J12") (pin "1") (pinfunction "1_1") (pintype "passive"))
      (node (ref "J13") (pin "1") (pinfunction "1_1") (pintype "passive"))
      (node (ref "J14") (pin "1") (pinfunction "1_1") (pintype "passive"))
      (node (ref "J15") (pin "1") (pinfunction "1_1") (pintype "passive"))
      (node (ref "J16") (pin "1") (pinfunction "1_1") (pintype "passive"))
      (node (ref "J17") (pin "1") (pinfunction "1_1") (pintype "passive"))
      (node (ref "J18") (pin "1") (pinfunction "1_1") (pintype "passive"))
      (node (ref "J19") (pin "1") (pinfunction "1_1") (pintype "passive"))
      (node (ref "J20") (pin "1") (pinfunction "1_1") (pintype "passive"))
      (node (ref "J21") (pin "1") (pinfunction "1_1") (pintype "passive"))
      (node (ref "J22") (pin "1") (pinfunction "1_1") (pintype "passive"))
      (node (ref "J7") (pin "1") (pinfunction "1_1") (pintype "passive"))
      (node (ref "J8") (pin "1") (pinfunction "1_1") (pintype "passive"))
      (node (ref "J9") (pin "1") (pinfunction "1_1") (pintype "passive"))
      (node (ref "R24") (pin "1") (pinfunction "1_1") (pintype "passive"))
      (node (ref "R25") (pin "1") (pinfunction "1_1") (pintype "passive"))
      (node (ref "R26") (pin "1") (pinfunction "1_1") (pintype "passive"))
      (node (ref "R27") (pin "1") (pinfunction "1_1") (pintype "passive"))
      (node (ref "R30") (pin "1") (pinfunction "1_1") (pintype "passive"))
      (node (ref "R31") (pin "1") (pinfunction "1_1") (pintype "passive"))
      (node (ref "R32") (pin "1") (pinfunction "1_1") (pintype "passive"))
      (node (ref "R33") (pin "1") (pinfunction "1_1") (pintype "passive"))
      (node (ref "R40") (pin "1") (pinfunction "1_1") (pintype "passive"))
      (node (ref "R41") (pin "1") (pinfunction "1_1") (pintype "passive"))
      (node (ref "R42") (pin "1") (pinfunction "1_1") (pintype "passive"))
      (node (ref "R43") (pin "1") (pinfunction "1_1") (pintype "passive"))
      (node (ref "R46") (pin "1") (pinfunction "1_1") (pintype "passive"))
      (node (ref "R47") (pin "1") (pinfunction "1_1") (pintype "passive"))
      (node (ref "R48") (pin "1") (pinfunction "1_1") (pintype "passive"))
      (node (ref "R49") (pin "1") (pinfunction "1_1") (pintype "passive"))
      (node (ref "R50") (pin "2") (pinfunction "3_2") (pintype "passive"))
      (node (ref "R51") (pin "2") (pinfunction "3_2") (pintype "passive"))
      (node (ref "R52") (pin "1") (pinfunction "2_1") (pintype "passive"))
      (node (ref "R53") (pin "2") (pinfunction "3_2") (pintype "passive"))
      (node (ref "R54") (pin "1") (pinfunction "2_1") (pintype "passive"))
      (node (ref "R55") (pin "1") (pinfunction "2_1") (pintype "passive"))
      (node (ref "R56") (pin "2") (pinfunction "3_2") (pintype "passive"))
      (node (ref "R57") (pin "1") (pinfunction "2_1") (pintype "passive"))
      (node (ref "R58") (pin "2") (pinfunction "3_2") (pintype "passive"))
      (node (ref "R59") (pin "2") (pinfunction "3_2") (pintype "passive"))
      (node (ref "R60") (pin "1") (pinfunction "2_1") (pintype "passive"))
      (node (ref "R61") (pin "2") (pinfunction "3_2") (pintype "passive"))
      (node (ref "R62") (pin "1") (pinfunction "2_1") (pintype "passive"))
      (node (ref "R63") (pin "2") (pinfunction "3_2") (pintype "passive"))
      (node (ref "R64") (pin "1") (pinfunction "2_1") (pintype "passive"))
      (node (ref "R65") (pin "1") (pinfunction "2_1") (pintype "passive"))
      (node (ref "U10") (pin "4") (pinfunction "GND_4") (pintype "passive"))
      (node (ref "U11") (pin "4") (pinfunction "GND_4") (pintype "passive"))
      (node (ref "U12") (pin "4") (pinfunction "GND_4") (pintype "passive"))
      (node (ref "U13") (pin "4") (pinfunction "GND_4") (pintype "passive"))
      (node (ref "U6") (pin "4") (pinfunction "GND_4") (pintype "passive"))
      (node (ref "U7") (pin "4") (pinfunction "GND_4") (pintype "passive"))
      (node (ref "U8") (pin "4") (pinfunction "GND_4") (pintype "passive"))
      (node (ref "U9") (pin "4") (pinfunction "GND_4") (pintype "passive"))
    )
    (net (code "19") (name "Net-(R6-2)") (class "Default")
      (node (ref "J12") (pin "2") (pinfunction "2_2") (pintype "passive"))
      (node (ref "R6") (pin "1") (pinfunction "2_1") (pintype "passive"))
    )
    (net (code "20") (name "Net-(R7-2)") (class "Default")
      (node (ref "J9") (pin "2") (pinfunction "2_2") (pintype "passive"))
      (node (ref "R7") (pin "1") (pinfunction "2_1") (pintype "passive"))
    )
    (net (code "21") (name "Net-(R8-2)") (class "Default")
      (node (ref "J10") (pin "2") (pinfunction "2_2") (pintype "passive"))
      (node (ref "R8") (pin "1") (pinfunction "2_1") (pintype "passive"))
    )
    (net (code "22") (name "Net-(R18-2)") (class "Default")
      (node (ref "R18") (pin "1") (pinfunction "2_1") (pintype "passive"))
      (node (ref "R24") (pin "2") (pinfunction "2_2") (pintype "passive"))
      (node (ref "U6") (pin "6") (pinfunction "2IN-_6") (pintype "passive"))
    )
    (net (code "23") (name "Net-(R18-3)") (class "Default")
      (node (ref "R18") (pin "2") (pinfunction "3_2") (pintype "passive"))
      (node (ref "R67") (pin "2") (pinfunction "3_2") (pintype "passive"))
      (node (ref "U6") (pin "7") (pinfunction "2OUT_7") (pintype "passive"))
    )
    (net (code "24") (name "Net-(R19-2)") (class "Default")
      (node (ref "R19") (pin "1") (pinfunction "2_1") (pintype "passive"))
      (node (ref "R25") (pin "2") (pinfunction "2_2") (pintype "passive"))
      (node (ref "U6") (pin "2") (pinfunction "1IN-_2") (pintype "passive"))
    )
    (net (code "25") (name "Net-(R19-3)") (class "Default")
      (node (ref "R19") (pin "2") (pinfunction "3_2") (pintype "passive"))
      (node (ref "R68") (pin "2") (pinfunction "3_2") (pintype "passive"))
      (node (ref "U6") (pin "1") (pinfunction "1OUT_1") (pintype "passive"))
    )
    (net (code "26") (name "Net-(R20-2)") (class "Default")
      (node (ref "R20") (pin "1") (pinfunction "2_1") (pintype "passive"))
      (node (ref "R26") (pin "2") (pinfunction "2_2") (pintype "passive"))
      (node (ref "U7") (pin "6") (pinfunction "2IN-_6") (pintype "passive"))
    )
    (net (code "27") (name "Net-(R20-3)") (class "Default")
      (node (ref "R20") (pin "2") (pinfunction "3_2") (pintype "passive"))
      (node (ref "R7") (pin "2") (pinfunction "3_2") (pintype "passive"))
      (node (ref "U7") (pin "7") (pinfunction "2OUT_7") (pintype "passive"))
    )
    (net (code "28") (name "Net-(R21-2)") (class "Default")
      (node (ref "R21") (pin "1") (pinfunction "2_1") (pintype "passive"))
      (node (ref "R27") (pin "2") (pinfunction "2_2") (pintype "passive"))
      (node (ref "U7") (pin "2") (pinfunction "1IN-_2") (pintype "passive"))
    )
    (net (code "29") (name "Net-(R21-3)") (class "Default")
      (node (ref "R21") (pin "2") (pinfunction "3_2") (pintype "passive"))
      (node (ref "R8") (pin "2") (pinfunction "3_2") (pintype "passive"))
      (node (ref "U7") (pin "1") (pinfunction "1OUT_1") (pintype "passive"))
    )
    (net (code "30") (name "Net-(R22-2)") (class "Default")
      (node (ref "R22") (pin "1") (pinfunction "2_1") (pintype "passive"))
      (node (ref "R30") (pin "2") (pinfunction "2_2") (pintype "passive"))
      (node (ref "U8") (pin "6") (pinfunction "2IN-_6") (pintype "passive"))
    )
    (net (code "31") (name "Net-(R22-3)") (class "Default")
      (node (ref "R22") (pin "2") (pinfunction "3_2") (pintype "passive"))
      (node (ref "R66") (pin "2") (pinfunction "3_2") (pintype "passive"))
      (node (ref "U8") (pin "7") (pinfunction "2OUT_7") (pintype "passive"))
    )
    (net (code "32") (name "Net-(R23-2)") (class "Default")
      (node (ref "R23") (pin "1") (pinfunction "2_1") (pintype "passive"))
      (node (ref "R31") (pin "2") (pinfunction "2_2") (pintype "passive"))
      (node (ref "U8") (pin "2") (pinfunction "1IN-_2") (pintype "passive"))
    )
    (net (code "33") (name "Net-(R23-3)") (class "Default")
      (node (ref "R23") (pin "2") (pinfunction "3_2") (pintype "passive"))
      (node (ref "R6") (pin "2") (pinfunction "3_2") (pintype "passive"))
      (node (ref "U8") (pin "1") (pinfunction "1OUT_1") (pintype "passive"))
    )
    (net (code "34") (name "Net-(R28-2)") (class "Default")
      (node (ref "R28") (pin "1") (pinfunction "2_1") (pintype "passive"))
      (node (ref "R32") (pin "2") (pinfunction "2_2") (pintype "passive"))
      (node (ref "U9") (pin "6") (pinfunction "2IN-_6") (pintype "passive"))
    )
    (net (code "35") (name "Net-(R28-3)") (class "Default")
      (node (ref "R28") (pin "2") (pinfunction "3_2") (pintype "passive"))
      (node (ref "R69") (pin "2") (pinfunction "3_2") (pintype "passive"))
      (node (ref "U9") (pin "7") (pinfunction "2OUT_7") (pintype "passive"))
    )
    (net (code "36") (name "Net-(R29-2)") (class "Default")
      (node (ref "R29") (pin "1") (pinfunction "2_1") (pintype "passive"))
      (node (ref "R33") (pin "2") (pinfunction "2_2") (pintype "passive"))
      (node (ref "U9") (pin "2") (pinfunction "1IN-_2") (pintype "passive"))
    )
    (net (code "37") (name "Net-(R29-3)") (class "Default")
      (node (ref "R29") (pin "2") (pinfunction "3_2") (pintype "passive"))
      (node (ref "R70") (pin "2") (pinfunction "3_2") (pintype "passive"))
      (node (ref "U9") (pin "1") (pinfunction "1OUT_1") (pintype "passive"))
    )
    (net (code "38") (name "Net-(R34-2)") (class "Default")
      (node (ref "R34") (pin "1") (pinfunction "2_1") (pintype "passive"))
      (node (ref "R40") (pin "2") (pinfunction "2_2") (pintype "passive"))
      (node (ref "U10") (pin "6") (pinfunction "2IN-_6") (pintype "passive"))
    )
    (net (code "39") (name "Net-(R34-3)") (class "Default")
      (node (ref "R34") (pin "2") (pinfunction "3_2") (pintype "passive"))
      (node (ref "R71") (pin "2") (pinfunction "3_2") (pintype "passive"))
      (node (ref "U10") (pin "7") (pinfunction "2OUT_7") (pintype "passive"))
    )
    (net (code "40") (name "Net-(R35-2)") (class "Default")
      (node (ref "R35") (pin "1") (pinfunction "2_1") (pintype "passive"))
      (node (ref "R41") (pin "2") (pinfunction "2_2") (pintype "passive"))
      (node (ref "U10") (pin "2") (pinfunction "1IN-_2") (pintype "passive"))
    )
    (net (code "41") (name "Net-(R35-3)") (class "Default")
      (node (ref "R35") (pin "2") (pinfunction "3_2") (pintype "passive"))
      (node (ref "R72") (pin "2") (pinfunction "3_2") (pintype "passive"))
      (node (ref "U10") (pin "1") (pinfunction "1OUT_1") (pintype "passive"))
    )
    (net (code "42") (name "Net-(R36-2)") (class "Default")
      (node (ref "R36") (pin "1") (pinfunction "2_1") (pintype "passive"))
      (node (ref "R42") (pin "2") (pinfunction "2_2") (pintype "passive"))
      (node (ref "U11") (pin "6") (pinfunction "2IN-_6") (pintype "passive"))
    )
    (net (code "43") (name "Net-(R36-3)") (class "Default")
      (node (ref "R36") (pin "2") (pinfunction "3_2") (pintype "passive"))
      (node (ref "R76") (pin "2") (pinfunction "3_2") (pintype "passive"))
      (node (ref "U11") (pin "7") (pinfunction "2OUT_7") (pintype "passive"))
    )
    (net (code "44") (name "Net-(R37-2)") (class "Default")
      (node (ref "R37") (pin "1") (pinfunction "2_1") (pintype "passive"))
      (node (ref "R43") (pin "2") (pinfunction "2_2") (pintype "passive"))
      (node (ref "U11") (pin "2") (pinfunction "1IN-_2") (pintype "passive"))
    )
    (net (code "45") (name "Net-(R37-3)") (class "Default")
      (node (ref "R37") (pin "2") (pinfunction "3_2") (pintype "passive"))
      (node (ref "R78") (pin "2") (pinfunction "3_2") (pintype "passive"))
      (node (ref "U11") (pin "1") (pinfunction "1OUT_1") (pintype "passive"))
    )
    (net (code "46") (name "Net-(R38-2)") (class "Default")
      (node (ref "R38") (pin "1") (pinfunction "2_1") (pintype "passive"))
      (node (ref "R46") (pin "2") (pinfunction "2_2") (pintype "passive"))
      (node (ref "U12") (pin "6") (pinfunction "2IN-_6") (pintype "passive"))
    )
    (net (code "47") (name "Net-(R38-3)") (class "Default")
      (node (ref "R38") (pin "2") (pinfunction "3_2") (pintype "passive"))
      (node (ref "R73") (pin "2") (pinfunction "3_2") (pintype "passive"))
      (node (ref "U12") (pin "7") (pinfunction "2OUT_7") (pintype "passive"))
    )
    (net (code "48") (name "Net-(R39-2)") (class "Default")
      (node (ref "R39") (pin "1") (pinfunction "2_1") (pintype "passive"))
      (node (ref "R47") (pin "2") (pinfunction "2_2") (pintype "passive"))
      (node (ref "U12") (pin "2") (pinfunction "1IN-_2") (pintype "passive"))
    )
    (net (code "49") (name "Net-(R39-3)") (class "Default")
      (node (ref "R39") (pin "2") (pinfunction "3_2") (pintype "passive"))
      (node (ref "R75") (pin "2") (pinfunction "3_2") (pintype "passive"))
      (node (ref "U12") (pin "1") (pinfunction "1OUT_1") (pintype "passive"))
    )
    (net (code "50") (name "Net-(R44-2)") (class "Default")
      (node (ref "R44") (pin "1") (pinfunction "2_1") (pintype "passive"))
      (node (ref "R48") (pin "2") (pinfunction "2_2") (pintype "passive"))
      (node (ref "U13") (pin "6") (pinfunction "2IN-_6") (pintype "passive"))
    )
    (net (code "51") (name "Net-(R44-3)") (class "Default")
      (node (ref "R44") (pin "2") (pinfunction "3_2") (pintype "passive"))
      (node (ref "R77") (pin "2") (pinfunction "3_2") (pintype "passive"))
      (node (ref "U13") (pin "7") (pinfunction "2OUT_7") (pintype "passive"))
    )
    (net (code "52") (name "Net-(R45-2)") (class "Default")
      (node (ref "R45") (pin "1") (pinfunction "2_1") (pintype "passive"))
      (node (ref "R49") (pin "2") (pinfunction "2_2") (pintype "passive"))
      (node (ref "U13") (pin "2") (pinfunction "1IN-_2") (pintype "passive"))
    )
    (net (code "53") (name "Net-(R45-3)") (class "Default")
      (node (ref "R45") (pin "2") (pinfunction "3_2") (pintype "passive"))
      (node (ref "R74") (pin "2") (pinfunction "3_2") (pintype "passive"))
      (node (ref "U13") (pin "1") (pinfunction "1OUT_1") (pintype "passive"))
    )
    (net (code "54") (name "Net-(R66-2)") (class "Default")
      (node (ref "J11") (pin "2") (pinfunction "2_2") (pintype "passive"))
      (node (ref "R66") (pin "1") (pinfunction "2_1") (pintype "passive"))
    )
    (net (code "55") (name "Net-(R67-2)") (class "Default")
      (node (ref "J7") (pin "2") (pinfunction "2_2") (pintype "passive"))
      (node (ref "R67") (pin "1") (pinfunction "2_1") (pintype "passive"))
    )
    (net (code "56") (name "Net-(R68-2)") (class "Default")
      (node (ref "J8") (pin "2") (pinfunction "2_2") (pintype "passive"))
      (node (ref "R68") (pin "1") (pinfunction "2_1") (pintype "passive"))
    )
    (net (code "57") (name "Net-(R69-2)") (class "Default")
      (node (ref "J13") (pin "2") (pinfunction "2_2") (pintype "passive"))
      (node (ref "R69") (pin "1") (pinfunction "2_1") (pintype "passive"))
    )
    (net (code "58") (name "Net-(R70-2)") (class "Default")
      (node (ref "J14") (pin "2") (pinfunction "2_2") (pintype "passive"))
      (node (ref "R70") (pin "1") (pinfunction "2_1") (pintype "passive"))
    )
    (net (code "59") (name "Net-(R71-2)") (class "Default")
      (node (ref "J15") (pin "2") (pinfunction "2_2") (pintype "passive"))
      (node (ref "R71") (pin "1") (pinfunction "2_1") (pintype "passive"))
    )
    (net (code "60") (name "Net-(R72-2)") (class "Default")
      (node (ref "J16") (pin "2") (pinfunction "2_2") (pintype "passive"))
      (node (ref "R72") (pin "1") (pinfunction "2_1") (pintype "passive"))
    )
    (net (code "61") (name "Net-(R73-2)") (class "Default")
      (node (ref "J19") (pin "2") (pinfunction "2_2") (pintype "passive"))
      (node (ref "R73") (pin "1") (pinfunction "2_1") (pintype "passive"))
    )
    (net (code "62") (name "Net-(R74-2)") (class "Default")
      (node (ref "J22") (pin "2") (pinfunction "2_2") (pintype "passive"))
      (node (ref "R74") (pin "1") (pinfunction "2_1") (pintype "passive"))
    )
    (net (code "63") (name "Net-(R75-2)") (class "Default")
      (node (ref "J20") (pin "2") (pinfunction "2_2") (pintype "passive"))
      (node (ref "R75") (pin "1") (pinfunction "2_1") (pintype "passive"))
    )
    (net (code "64") (name "Net-(R76-2)") (class "Default")
      (node (ref "J17") (pin "2") (pinfunction "2_2") (pintype "passive"))
      (node (ref "R76") (pin "1") (pinfunction "2_1") (pintype "passive"))
    )
    (net (code "65") (name "Net-(R77-2)") (class "Default")
      (node (ref "J21") (pin "2") (pinfunction "2_2") (pintype "passive"))
      (node (ref "R77") (pin "1") (pinfunction "2_1") (pintype "passive"))
    )
    (net (code "66") (name "Net-(R78-2)") (class "Default")
      (node (ref "J18") (pin "2") (pinfunction "2_2") (pintype "passive"))
      (node (ref "R78") (pin "1") (pinfunction "2_1") (pintype "passive"))
    )
  )
)
